# circuitDiagramEasyEDA.net
KiCad netlist of a schematic drawn in EasyEDA
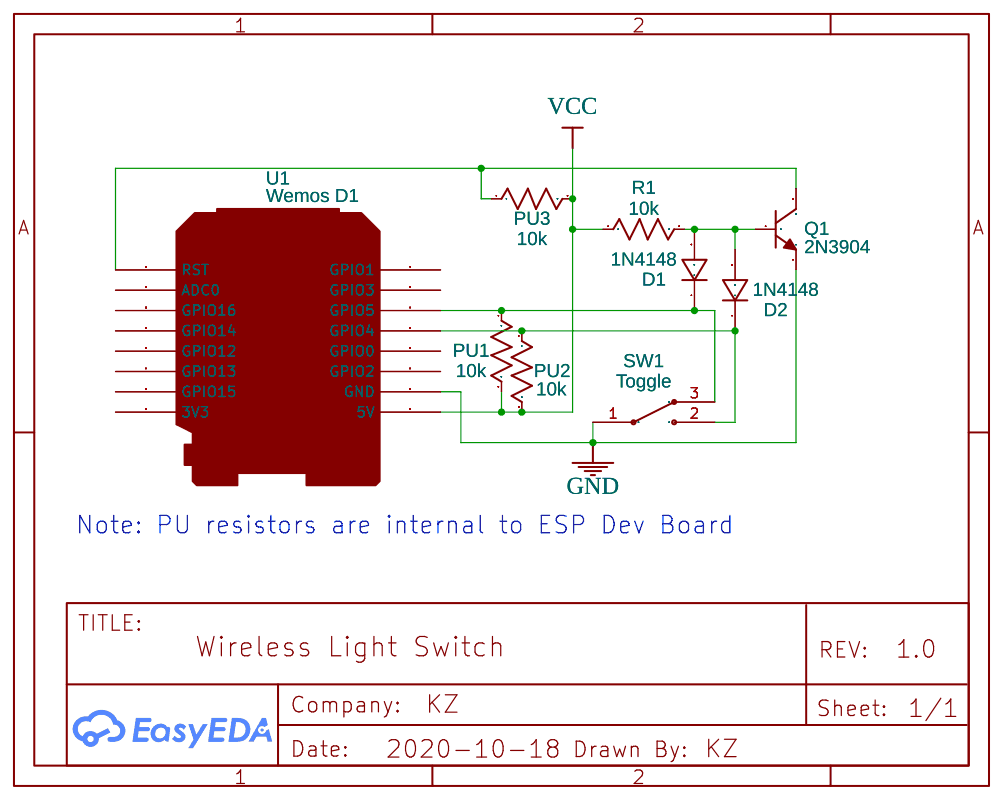
[diagram p0: schematic sheet]

(export (version "E")
  (design (tool "Eeschema 10.0.6"))
  (components
    (comp (ref "D1")
      (value "1N4148")
      (fields (field (name "BOM_Manufacturer Part") "1N4007W") (field (name "BOM_Supplier Part") "C328592"))
      (libsource (lib "") (part "1N4007W"))
    )
    (comp (ref "D2")
      (value "1N4148")
      (fields (field (name "BOM_Manufacturer Part") "1N4007W") (field (name "BOM_Supplier Part") "C328592"))
      (libsource (lib "") (part "1N4007W"))
    )
    (comp (ref "PU1") (value "10k") (libsource (lib "") (part "R_0603_US_2")))
    (comp (ref "PU2") (value "10k") (libsource (lib "") (part "R_0603_US_2")))
    (comp (ref "PU3") (value "10k") (libsource (lib "") (part "R_0603_US_1")))
    (comp (ref "Q1")
      (value "2N3904")
      (fields (field (name "BOM_Supplier Part") "C118538"))
      (libsource (lib "") (part "2N3904"))
    )
    (comp (ref "R1") (value "10k") (libsource (lib "") (part "R_0603_US")))
    (comp (ref "SW1")
      (value "Toggle")
      (fields
        (field (name "BOM_Manufacturer Part") "MSK-11027 Toggle Switches")
        (field (name "BOM_Supplier Part") "C21381")
      )
      (libsource (lib "") (part "MSK-11027 Toggle Switches"))
    )
    (comp (ref "U1") (value "Wemos D1") (libsource (lib "") (part "Wemos D1")))
  )
  (nets
    (net (code "1") (name "GND") (class "Default")
      (node (ref "Q1") (pin "1") (pinfunction "E_1") (pintype "unspecified"))
      (node (ref "SW1") (pin "1") (pinfunction "2_1") (pintype "unspecified"))
      (node (ref "U1") (pin "GND") (pinfunction "GND_GND") (pintype "passive"))
    )
    (net (code "2") (name "Net-(Q1-B)") (class "Default")
      (node (ref "D1") (pin "2") (pinfunction "2_2") (pintype "unspecified"))
      (node (ref "D2") (pin "2") (pinfunction "2_2") (pintype "unspecified"))
      (node (ref "Q1") (pin "2") (pinfunction "B_2") (pintype "unspecified"))
      (node (ref "R1") (pin "2") (pinfunction "2_2") (pintype "unspecified"))
    )
    (net (code "3") (name "Net-(Q1-C)") (class "Default")
      (node (ref "PU3") (pin "1") (pinfunction "1_1") (pintype "unspecified"))
      (node (ref "Q1") (pin "3") (pinfunction "C_3") (pintype "unspecified"))
      (node (ref "U1") (pin "RST") (pinfunction "RST_RST") (pintype "input"))
    )
    (net (code "4") (name "Net-(SW1-1)") (class "Default")
      (node (ref "D2") (pin "1") (pinfunction "1_1") (pintype "unspecified"))
      (node (ref "PU2") (pin "1") (pinfunction "1_1") (pintype "unspecified"))
      (node (ref "SW1") (pin "2") (pinfunction "1_2") (pintype "unspecified"))
      (node (ref "U1") (pin "D2") (pinfunction "GPIO4_D2") (pintype "bidirectional"))
    )
    (net (code "5") (name "Net-(U1-GPIO5)") (class "Default")
      (node (ref "D1") (pin "1") (pinfunction "1_1") (pintype "unspecified"))
      (node (ref "PU1") (pin "1") (pinfunction "1_1") (pintype "unspecified"))
      (node (ref "SW1") (pin "3") (pinfunction "3_3") (pintype "unspecified"))
      (node (ref "U1") (pin "D1") (pinfunction "GPIO5_D1") (pintype "bidirectional"))
    )
    (net (code "6") (name "VCC") (class "Default")
      (node (ref "PU1") (pin "2") (pinfunction "2_2") (pintype "unspecified"))
      (node (ref "PU2") (pin "2") (pinfunction "2_2") (pintype "unspecified"))
      (node (ref "PU3") (pin "2") (pinfunction "2_2") (pintype "unspecified"))
      (node (ref "R1") (pin "1") (pinfunction "1_1") (pintype "unspecified"))
      (node (ref "U1") (pin "5V") (pinfunction "5V_5V") (pintype "passive"))
    )
    (net (code "7") (name "unconnected-(U1-ADC0-PadA0)") (class "Default")
      (node (ref "U1") (pin "A0") (pinfunction "ADC0_A0") (pintype "input"))
    )
    (net (code "8") (name "unconnected-(U1-GPIO0-PadD3)") (class "Default")
      (node (ref "U1") (pin "D3") (pinfunction "GPIO0_D3") (pintype "bidirectional"))
    )
    (net (code "9") (name "unconnected-(U1-GPIO1-PadTX)") (class "Default")
      (node (ref "U1") (pin "TX") (pinfunction "GPIO1_TX") (pintype "bidirectional"))
    )
    (net (code "10") (name "unconnected-(U1-GPIO2-PadD4)") (class "Default")
      (node (ref "U1") (pin "D4") (pinfunction "GPIO2_D4") (pintype "bidirectional"))
    )
    (net (code "11") (name "unconnected-(U1-GPIO3-PadRX)") (class "Default")
      (node (ref "U1") (pin "RX") (pinfunction "GPIO3_RX") (pintype "bidirectional"))
    )
    (net (code "12") (name "unconnected-(U1-GPIO12-PadD6)") (class "Default")
      (node (ref "U1") (pin "D6") (pinfunction "GPIO12_D6") (pintype "bidirectional"))
    )
    (net (code "13") (name "unconnected-(U1-GPIO13-PadD7)") (class "Default")
      (node (ref "U1") (pin "D7") (pinfunction "GPIO13_D7") (pintype "bidirectional"))
    )
    (net (code "14") (name "unconnected-(U1-GPIO14-PadD2)") (class "Default")
      (node (ref "U1") (pin "D2") (pinfunction "GPIO14_D2") (pintype "bidirectional"))
    )
    (net (code "15") (name "unconnected-(U1-GPIO15-PadD8)") (class "Default")
      (node (ref "U1") (pin "D8") (pinfunction "GPIO15_D8") (pintype "bidirectional"))
    )
    (net (code "16") (name "unconnected-(U1-GPIO16-PadD0)") (class "Default")
      (node (ref "U1") (pin "D0") (pinfunction "GPIO16_D0") (pintype "bidirectional"))
    )
    (net (code "17") (name "unconnected-(U1-Pad3V3)") (class "Default")
      (node (ref "U1") (pin "3V3") (pinfunction "3V3_3V3") (pintype "passive"))
    )
  )
)
